# Regulador_5v_FF21.net
KiCad netlist of a schematic drawn in Altium Designer
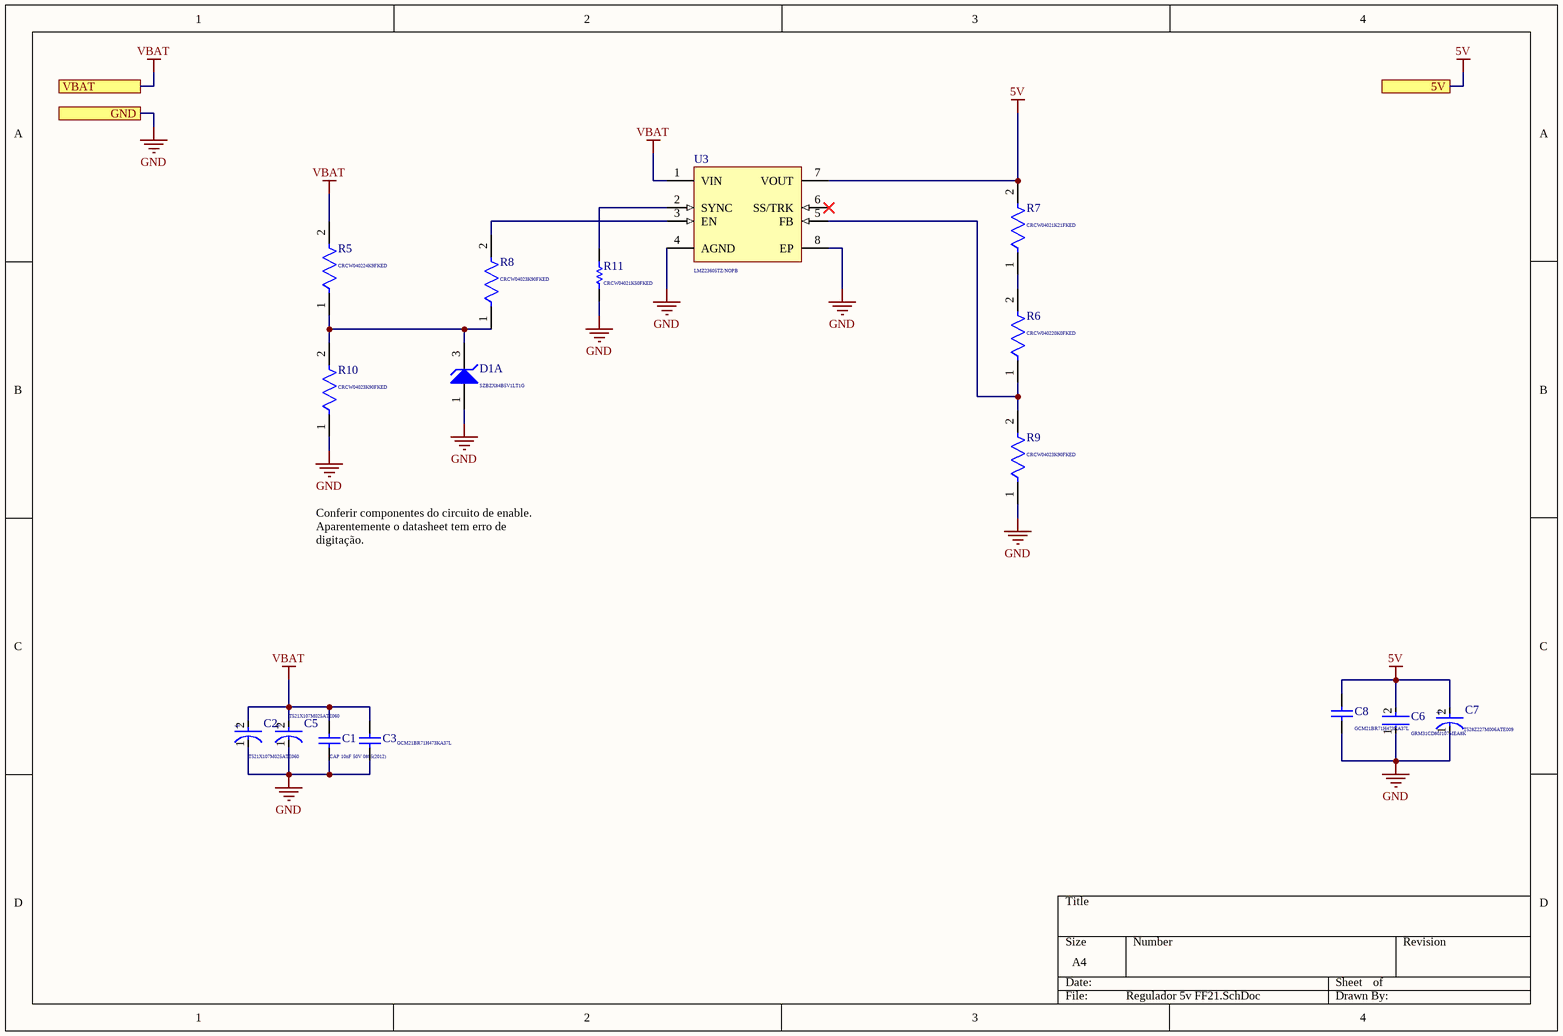
[diagram p0: Regulador 5v FF21.SchDoc]

(export (version "E")
  (design (tool "Eeschema 10.0.6"))
  (components
    (comp (ref "C1")
      (value "CAP 10nF 50V 0805(2012)")
      (footprint "CAPC0805(2012)75_N")
      (description "CAP 10nF 50V ±5% 0805 (2012 Metric) Thickness 0.75mm SMD")
      (fields (field (name "TOLERANCE") "Â±5%"))
      (libsource (lib "Altium Content Vault") (part "CAP"))
    )
    (comp (ref "C2")
      (value "T521X107M025ATE060")
      (footprint "FP-T521X-MFG")
      (description "CAP TANT POLY 100UF 25V 2917")
      (fields (field (name "TOLERANCE") "20%"))
      (libsource (lib "Altium Content Vault") (part "cf48714ba7e38822c1575c7ec0b6d1f"))
    )
    (comp (ref "C3")
      (value "GCM21BR71H473KA37L")
      (footprint "CAPC2013X140X45ML15T25")
      (fields (field (name "MANUFACTURER") "Murata"))
      (libsource (lib "Altium Content Vault") (part "CAP"))
    )
    (comp (ref "C5")
      (value "T521X107M025ATE060")
      (footprint "FP-T521X-MFG")
      (description "CAP TANT POLY 100UF 25V 2917")
      (fields (field (name "TOLERANCE") "20%"))
      (libsource (lib "Altium Content Vault") (part "cf48714ba7e38822c1575c7ec0b6d1f"))
    )
    (comp (ref "C6")
      (value "GRM31CD80J107MEA8K")
      (footprint "FP-GRM31C-0_3-e0_3_0_8-IPC_A")
      (description "Chip Multilayer Ceramic Capacitors for General Purpose, 1206, 100uF, X6T, +22%/-33%, 20%, 6.3V")
      (libsource (lib "Altium Content Vault") (part "f23184f103b6ebe33a8c269c53dcba6"))
    )
    (comp (ref "C7")
      (value "T528Z227M006ATE009")
      (footprint "FP-T528Z227M006ATE009-MFG")
      (description "CAP TANT POLY 220UF 6.3V 2917")
      (fields (field (name "TOLERANCE") "20%"))
      (libsource (lib "Altium Content Vault") (part "203bc49f2ac43e59fd269a8c329ed05"))
    )
    (comp (ref "C8")
      (value "GCM21BR71H473KA37L")
      (footprint "CAPC2013X140X45ML15T25")
      (fields (field (name "MANUFACTURER") "Murata"))
      (libsource (lib "Altium Content Vault") (part "CAP"))
    )
    (comp (ref "D1")
      (value "SZBZX84B5V1LT1G")
      (footprint "ONSC-SOT-23-3-318-08_V")
      (description "Zener Voltage Regulator, 225 mW, 3-Pin SOT-23, Pb-Free, Tape and Reel")
      (fields (field (name "MANUFACTURER") "On Semiconductor"))
      (libsource (lib "Altium Content Vault") (part "ONSC-A1K3-3"))
    )
    (comp (ref "R5")
      (value "CRCW040224K9FKED")
      (footprint "FP-CRCW0402-e3-IPC_C")
      (description "RES Thick Film, 24.9kΩ, 1%, 0.063W, 100ppm/°C, 0402")
      (fields (field (name "TOLERANCE") "1%"))
      (libsource (lib "Altium Content Vault") (part "1029c3af85768c4190bb7ad29bc67b5"))
    )
    (comp (ref "R6")
      (value "CRCW040220K0FKED")
      (footprint "FP-CRCW0402-e3-IPC_B")
      (description "RES Thick Film, 20kΩ, 1%, 0.063W, 100ppm/°C, 0402")
      (fields (field (name "TOLERANCE") "1%"))
      (libsource (lib "Altium Content Vault") (part "1029c3af85768c4190bb7ad29bc67b5"))
    )
    (comp (ref "R7")
      (value "CRCW04021K21FKED")
      (footprint "FP-CRCW0402-e3-IPC_B")
      (description "RES Thick Film, 1.21kΩ, 1%, 0.063W, 100ppm/°C, 0402")
      (fields (field (name "TOLERANCE") "1%"))
      (libsource (lib "Altium Content Vault") (part "1029c3af85768c4190bb7ad29bc67b5"))
    )
    (comp (ref "R8")
      (value "CRCW04023K90FKED")
      (footprint "FP-CRCW0402-e3-MFG")
      (description "RES Thick Film, 3.9kΩ, 1%, 0.063W, 100ppm/°C, 0402")
      (fields (field (name "TOLERANCE") "1%"))
      (libsource (lib "Altium Content Vault") (part "1029c3af85768c4190bb7ad29bc67b5"))
    )
    (comp (ref "R9")
      (value "CRCW04023K90FKED")
      (footprint "FP-CRCW0402-e3-MFG")
      (description "RES Thick Film, 3.9kΩ, 1%, 0.063W, 100ppm/°C, 0402")
      (fields (field (name "TOLERANCE") "1%"))
      (libsource (lib "Altium Content Vault") (part "1029c3af85768c4190bb7ad29bc67b5"))
    )
    (comp (ref "R10")
      (value "CRCW04023K90FKED")
      (footprint "FP-CRCW0402-e3-MFG")
      (description "RES Thick Film, 3.9kΩ, 1%, 0.063W, 100ppm/°C, 0402")
      (fields (field (name "TOLERANCE") "1%"))
      (libsource (lib "Altium Content Vault") (part "1029c3af85768c4190bb7ad29bc67b5"))
    )
    (comp (ref "R11")
      (value "CRCW04021K50FKED")
      (footprint "RESC1005X40X25NL05T05")
      (fields (field (name "MANUFACTURER") "Vishay Dale"))
      (libsource (lib "Altium Content Vault") (part "RES"))
    )
    (comp (ref "U3")
      (value "LMZ23605TZ/NOPB")
      (footprint "NDW0007A_V")
      (description "5A SIMPLE SWITCHER® Power Module with 36V Maximum Input Voltage, 7 pin TO-PMOD, 45 Rail")
      (fields (field (name "MANUFACTURER") "Texas Instruments"))
      (libsource (lib "Altium Content Vault") (part "PM-REG-LMZ23605-8"))
    )
  )
  (nets
    (net (code "1") (name "5V") (class "Default")
      (node (ref "C6") (pin "2") (pinfunction "2_2") (pintype "passive"))
      (node (ref "C7") (pin "2") (pinfunction "A_2") (pintype "passive"))
      (node (ref "C8") (pin "2") (pinfunction "2_2") (pintype "passive"))
      (node (ref "R7") (pin "2") (pinfunction "2_2") (pintype "passive"))
      (node (ref "U3") (pin "7") (pinfunction "VOUT_7") (pintype "power_in"))
    )
    (net (code "2") (name "GND") (class "Default")
      (node (ref "C1") (pin "1") (pinfunction "1_1") (pintype "passive"))
      (node (ref "C2") (pin "1") (pinfunction "C_1") (pintype "passive"))
      (node (ref "C3") (pin "1") (pinfunction "1_1") (pintype "passive"))
      (node (ref "C5") (pin "1") (pinfunction "C_1") (pintype "passive"))
      (node (ref "C6") (pin "1") (pinfunction "1_1") (pintype "passive"))
      (node (ref "C7") (pin "1") (pinfunction "C_1") (pintype "passive"))
      (node (ref "C8") (pin "1") (pinfunction "1_1") (pintype "passive"))
      (node (ref "D1") (pin "1") (pinfunction "A_1") (pintype "passive"))
      (node (ref "R10") (pin "1") (pinfunction "1_1") (pintype "passive"))
      (node (ref "R11") (pin "1") (pinfunction "1_1") (pintype "passive"))
      (node (ref "R9") (pin "1") (pinfunction "1_1") (pintype "passive"))
      (node (ref "U3") (pin "4") (pinfunction "AGND_4") (pintype "power_in"))
      (node (ref "U3") (pin "8") (pinfunction "EP_8") (pintype "power_in"))
    )
    (net (code "3") (name "Net-(D1A-K)") (class "Default")
      (node (ref "D1") (pin "3") (pinfunction "K_3") (pintype "passive"))
      (node (ref "R10") (pin "2") (pinfunction "2_2") (pintype "passive"))
      (node (ref "R5") (pin "1") (pinfunction "1_1") (pintype "passive"))
      (node (ref "R8") (pin "1") (pinfunction "1_1") (pintype "passive"))
    )
    (net (code "4") (name "Net-(R6-Pad2)") (class "Default")
      (node (ref "R6") (pin "2") (pinfunction "2_2") (pintype "passive"))
      (node (ref "R7") (pin "1") (pinfunction "1_1") (pintype "passive"))
    )
    (net (code "5") (name "Net-(U3-EN)") (class "Default")
      (node (ref "R8") (pin "2") (pinfunction "2_2") (pintype "passive"))
      (node (ref "U3") (pin "3") (pinfunction "EN_3") (pintype "input"))
    )
    (net (code "6") (name "Net-(U3-FB)") (class "Default")
      (node (ref "R6") (pin "1") (pinfunction "1_1") (pintype "passive"))
      (node (ref "R9") (pin "2") (pinfunction "2_2") (pintype "passive"))
      (node (ref "U3") (pin "5") (pinfunction "FB_5") (pintype "input"))
    )
    (net (code "7") (name "Net-(U3-SYNC)") (class "Default")
      (node (ref "R11") (pin "2") (pinfunction "2_2") (pintype "passive"))
      (node (ref "U3") (pin "2") (pinfunction "SYNC_2") (pintype "input"))
    )
    (net (code "8") (name "VBAT") (class "Default")
      (node (ref "C1") (pin "2") (pinfunction "2_2") (pintype "passive"))
      (node (ref "C2") (pin "2") (pinfunction "A_2") (pintype "passive"))
      (node (ref "C3") (pin "2") (pinfunction "2_2") (pintype "passive"))
      (node (ref "C5") (pin "2") (pinfunction "A_2") (pintype "passive"))
      (node (ref "R5") (pin "2") (pinfunction "2_2") (pintype "passive"))
      (node (ref "U3") (pin "1") (pinfunction "VIN_1") (pintype "power_in"))
    )
    (net (code "9") (name "unconnected-(U3-SS{slash}TRK-Pad6)") (class "Default")
      (node (ref "U3") (pin "6") (pinfunction "SS/TRK_6") (pintype "input+no_connect"))
    )
  )
)
